# ClockBox_OLED_addon.net
KiCad netlist of a schematic drawn in EAGLE
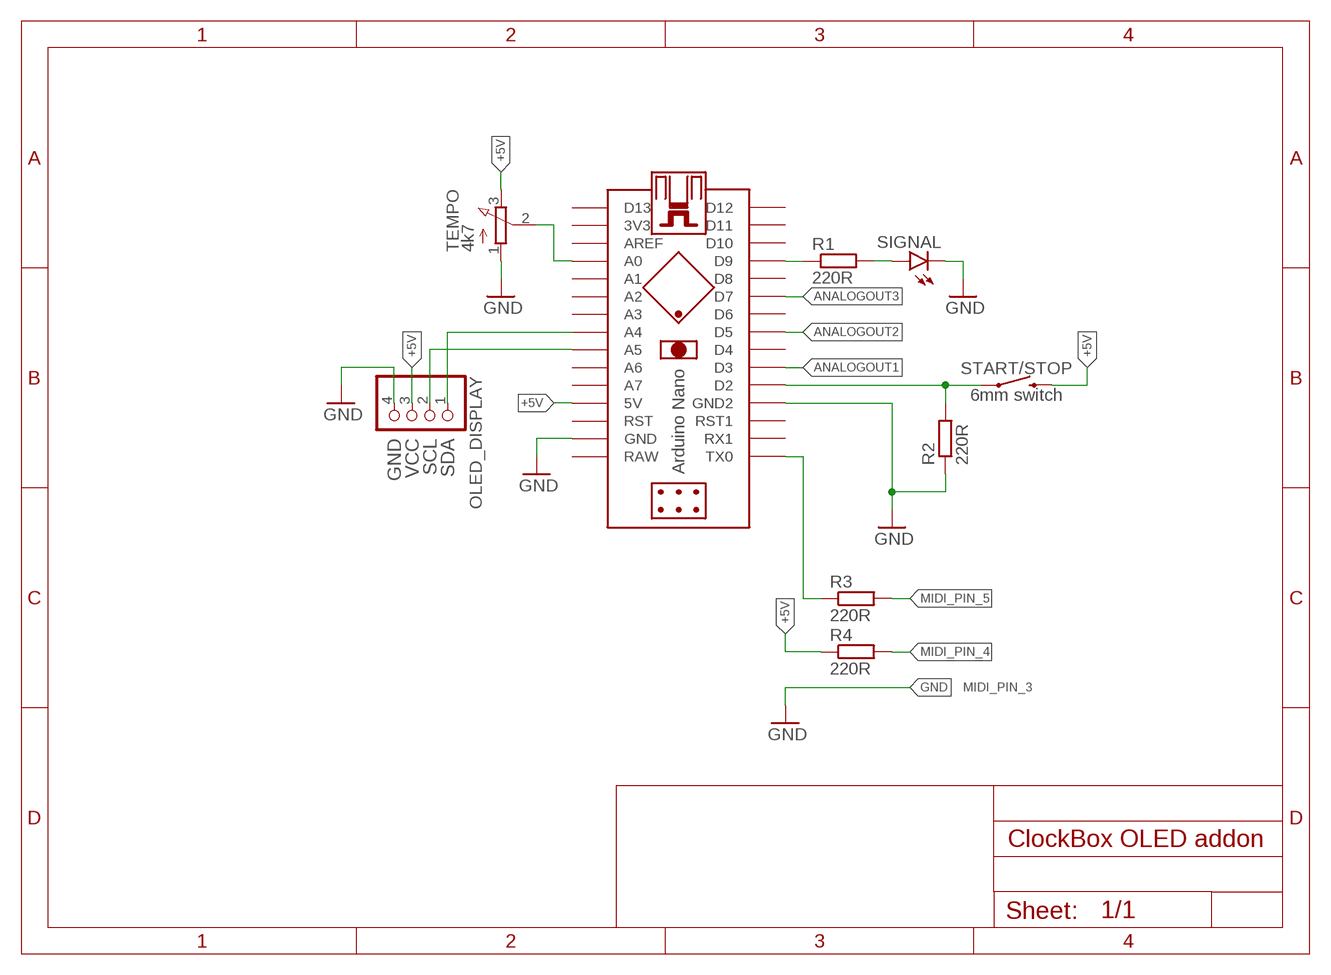
[diagram p0: schematic, sheet 1]

(export (version "E")
  (design (tool "Eeschema 10.0.6"))
  (components
    (comp (ref "OLED_DISPLAY")
      (value "PINHD-1X4")
      (footprint "eagle-import:1X04")
      (libsource (lib "eagle-import") (part "PINHD-1X4"))
    )
    (comp (ref "R1")
      (value "220R")
      (footprint "eagle-import:0204_7")
      (libsource (lib "eagle-import") (part "R-EU_0204/7"))
    )
    (comp (ref "R2")
      (value "220R")
      (footprint "eagle-import:0204_7")
      (libsource (lib "eagle-import") (part "R-EU_0204/7"))
    )
    (comp (ref "R3")
      (value "220R")
      (footprint "eagle-import:0204_7")
      (libsource (lib "eagle-import") (part "R-EU_0204/7"))
    )
    (comp (ref "R4")
      (value "220R")
      (footprint "eagle-import:0204_7")
      (libsource (lib "eagle-import") (part "R-EU_0204/7"))
    )
    (comp (ref "SIGNAL")
      (value "LED5MM")
      (footprint "eagle-import:LED5MM")
      (libsource (lib "eagle-import") (part "LED5MM"))
    )
    (comp (ref "START/STOP")
      (value "6mm switch")
      (footprint "eagle-import:TACTILE_SWITCH_PTH_6.0MM")
      (libsource (lib "eagle-import") (part "MOMENTARY-SWITCH-SPST-PTH-6.0MM"))
    )
    (comp (ref "TEMPO")
      (value "4k7")
      (footprint "eagle-import:3RP_1610N")
      (libsource (lib "eagle-import") (part "3RP/1610N"))
    )
    (comp (ref "U$1")
      (value "NANO")
      (footprint "eagle-import:NANO")
      (libsource (lib "eagle-import") (part "NANO"))
    )
  )
  (nets
    (net (code "1") (name "+5V") (class "Default")
      (node (ref "OLED_DISPLAY") (pin "3") (pinfunction "3_3") (pintype "passive"))
      (node (ref "R4") (pin "1") (pinfunction "1_1") (pintype "passive"))
      (node (ref "START/STOP") (pin "3") (pinfunction "2_3") (pintype "passive"))
      (node (ref "TEMPO") (pin "3") (pinfunction "E_3") (pintype "passive"))
      (node (ref "U$1") (pin "5V") (pinfunction "5V_5V") (pintype "bidirectional"))
    )
    (net (code "2") (name "ANALOGOUT1") (class "Default")
      (node (ref "U$1") (pin "D3") (pinfunction "D3_D3") (pintype "bidirectional"))
    )
    (net (code "3") (name "ANALOGOUT2") (class "Default")
      (node (ref "U$1") (pin "D5") (pinfunction "D5_D5") (pintype "bidirectional"))
    )
    (net (code "4") (name "ANALOGOUT3") (class "Default")
      (node (ref "U$1") (pin "D7") (pinfunction "D7_D7") (pintype "bidirectional"))
    )
    (net (code "5") (name "GND") (class "Default")
      (node (ref "OLED_DISPLAY") (pin "4") (pinfunction "4_4") (pintype "passive"))
      (node (ref "R2") (pin "1") (pinfunction "1_1") (pintype "passive"))
      (node (ref "SIGNAL") (pin "K") (pinfunction "C_K") (pintype "passive"))
      (node (ref "TEMPO") (pin "1") (pinfunction "A_1") (pintype "passive"))
      (node (ref "U$1") (pin "GND") (pinfunction "GND_GND") (pintype "bidirectional"))
      (node (ref "U$1") (pin "GND1") (pinfunction "GND2_GND1") (pintype "bidirectional"))
    )
    (net (code "6") (name "MIDI_PIN_4") (class "Default")
      (node (ref "R4") (pin "2") (pinfunction "2_2") (pintype "passive"))
    )
    (net (code "7") (name "MIDI_PIN_5") (class "Default")
      (node (ref "R3") (pin "2") (pinfunction "2_2") (pintype "passive"))
    )
    (net (code "8") (name "Net-(OLED_DISPLAY-Pad1)") (class "Default")
      (node (ref "OLED_DISPLAY") (pin "1") (pinfunction "1_1") (pintype "passive"))
      (node (ref "U$1") (pin "A4") (pinfunction "A4_A4") (pintype "bidirectional"))
    )
    (net (code "9") (name "Net-(OLED_DISPLAY-Pad2)") (class "Default")
      (node (ref "OLED_DISPLAY") (pin "2") (pinfunction "2_2") (pintype "passive"))
      (node (ref "U$1") (pin "A5") (pinfunction "A5_A5") (pintype "bidirectional"))
    )
    (net (code "10") (name "Net-(R1-Pad1)") (class "Default")
      (node (ref "R1") (pin "1") (pinfunction "1_1") (pintype "passive"))
      (node (ref "U$1") (pin "D9") (pinfunction "D9_D9") (pintype "bidirectional"))
    )
    (net (code "11") (name "Net-(R1-Pad2)") (class "Default")
      (node (ref "R1") (pin "2") (pinfunction "2_2") (pintype "passive"))
      (node (ref "SIGNAL") (pin "A") (pinfunction "A_A") (pintype "passive"))
    )
    (net (code "12") (name "Net-(R2-Pad2)") (class "Default")
      (node (ref "R2") (pin "2") (pinfunction "2_2") (pintype "passive"))
      (node (ref "START/STOP") (pin "1") (pinfunction "1_1") (pintype "passive"))
      (node (ref "U$1") (pin "D2") (pinfunction "D2_D2") (pintype "bidirectional"))
    )
    (net (code "13") (name "Net-(R3-Pad1)") (class "Default")
      (node (ref "R3") (pin "1") (pinfunction "1_1") (pintype "passive"))
      (node (ref "U$1") (pin "TX0") (pinfunction "TX0_TX0") (pintype "bidirectional"))
    )
    (net (code "14") (name "Net-(TEMPO-S)") (class "Default")
      (node (ref "TEMPO") (pin "2") (pinfunction "S_2") (pintype "passive"))
      (node (ref "U$1") (pin "A0") (pinfunction "A0_A0") (pintype "bidirectional"))
    )
    (net (code "15") (name "unconnected-(U$1-3V3-Pad3.3V)") (class "Default")
      (node (ref "U$1") (pin "3.3V") (pinfunction "3V3_3.3V") (pintype "bidirectional"))
    )
    (net (code "16") (name "unconnected-(U$1-PadA1)") (class "Default")
      (node (ref "U$1") (pin "A1") (pinfunction "A1_A1") (pintype "bidirectional"))
    )
    (net (code "17") (name "unconnected-(U$1-PadA2)") (class "Default")
      (node (ref "U$1") (pin "A2") (pinfunction "A2_A2") (pintype "bidirectional"))
    )
    (net (code "18") (name "unconnected-(U$1-PadA3)") (class "Default")
      (node (ref "U$1") (pin "A3") (pinfunction "A3_A3") (pintype "bidirectional"))
    )
    (net (code "19") (name "unconnected-(U$1-PadA6)") (class "Default")
      (node (ref "U$1") (pin "A6") (pinfunction "A6_A6") (pintype "bidirectional"))
    )
    (net (code "20") (name "unconnected-(U$1-PadA7)") (class "Default")
      (node (ref "U$1") (pin "A7") (pinfunction "A7_A7") (pintype "bidirectional"))
    )
    (net (code "21") (name "unconnected-(U$1-PadAREF)") (class "Default")
      (node (ref "U$1") (pin "AREF") (pinfunction "AREF_AREF") (pintype "bidirectional"))
    )
    (net (code "22") (name "unconnected-(U$1-PadD4)") (class "Default")
      (node (ref "U$1") (pin "D4") (pinfunction "D4_D4") (pintype "bidirectional"))
    )
    (net (code "23") (name "unconnected-(U$1-PadD6)") (class "Default")
      (node (ref "U$1") (pin "D6") (pinfunction "D6_D6") (pintype "bidirectional"))
    )
    (net (code "24") (name "unconnected-(U$1-PadD8)") (class "Default")
      (node (ref "U$1") (pin "D8") (pinfunction "D8_D8") (pintype "bidirectional"))
    )
    (net (code "25") (name "unconnected-(U$1-PadD10)") (class "Default")
      (node (ref "U$1") (pin "D10") (pinfunction "D10_D10") (pintype "bidirectional"))
    )
    (net (code "26") (name "unconnected-(U$1-PadD11)") (class "Default")
      (node (ref "U$1") (pin "D11") (pinfunction "D11_D11") (pintype "bidirectional"))
    )
    (net (code "27") (name "unconnected-(U$1-PadD12)") (class "Default")
      (node (ref "U$1") (pin "D12") (pinfunction "D12_D12") (pintype "bidirectional"))
    )
    (net (code "28") (name "unconnected-(U$1-PadD13)") (class "Default")
      (node (ref "U$1") (pin "D13") (pinfunction "D13_D13") (pintype "bidirectional"))
    )
    (net (code "29") (name "unconnected-(U$1-PadICSP1)") (class "Default")
      (node (ref "U$1") (pin "ICSP1") (pinfunction "ICSP1_ICSP1") (pintype "bidirectional"))
    )
    (net (code "30") (name "unconnected-(U$1-PadICSP2)") (class "Default")
      (node (ref "U$1") (pin "ICSP2") (pinfunction "ICSP2_ICSP2") (pintype "bidirectional"))
    )
    (net (code "31") (name "unconnected-(U$1-PadICSP3)") (class "Default")
      (node (ref "U$1") (pin "ICSP3") (pinfunction "ICSP3_ICSP3") (pintype "bidirectional"))
    )
    (net (code "32") (name "unconnected-(U$1-PadICSP4)") (class "Default")
      (node (ref "U$1") (pin "ICSP4") (pinfunction "ICSP4_ICSP4") (pintype "bidirectional"))
    )
    (net (code "33") (name "unconnected-(U$1-PadICSP5)") (class "Default")
      (node (ref "U$1") (pin "ICSP5") (pinfunction "ICSP5_ICSP5") (pintype "bidirectional"))
    )
    (net (code "34") (name "unconnected-(U$1-PadICSP6)") (class "Default")
      (node (ref "U$1") (pin "ICSP6") (pinfunction "ICSP6_ICSP6") (pintype "bidirectional"))
    )
    (net (code "35") (name "unconnected-(U$1-PadRAW)") (class "Default")
      (node (ref "U$1") (pin "RAW") (pinfunction "RAW_RAW") (pintype "bidirectional"))
    )
    (net (code "36") (name "unconnected-(U$1-PadRST)") (class "Default")
      (node (ref "U$1") (pin "RST") (pinfunction "RST_RST") (pintype "bidirectional"))
    )
    (net (code "37") (name "unconnected-(U$1-PadRST1)") (class "Default")
      (node (ref "U$1") (pin "RST1") (pinfunction "RST1_RST1") (pintype "bidirectional"))
    )
    (net (code "38") (name "unconnected-(U$1-PadRX1)") (class "Default")
      (node (ref "U$1") (pin "RX1") (pinfunction "RX1_RX1") (pintype "bidirectional"))
    )
  )
)
